# main.net
KiCad netlist of a schematic drawn in Altium Designer
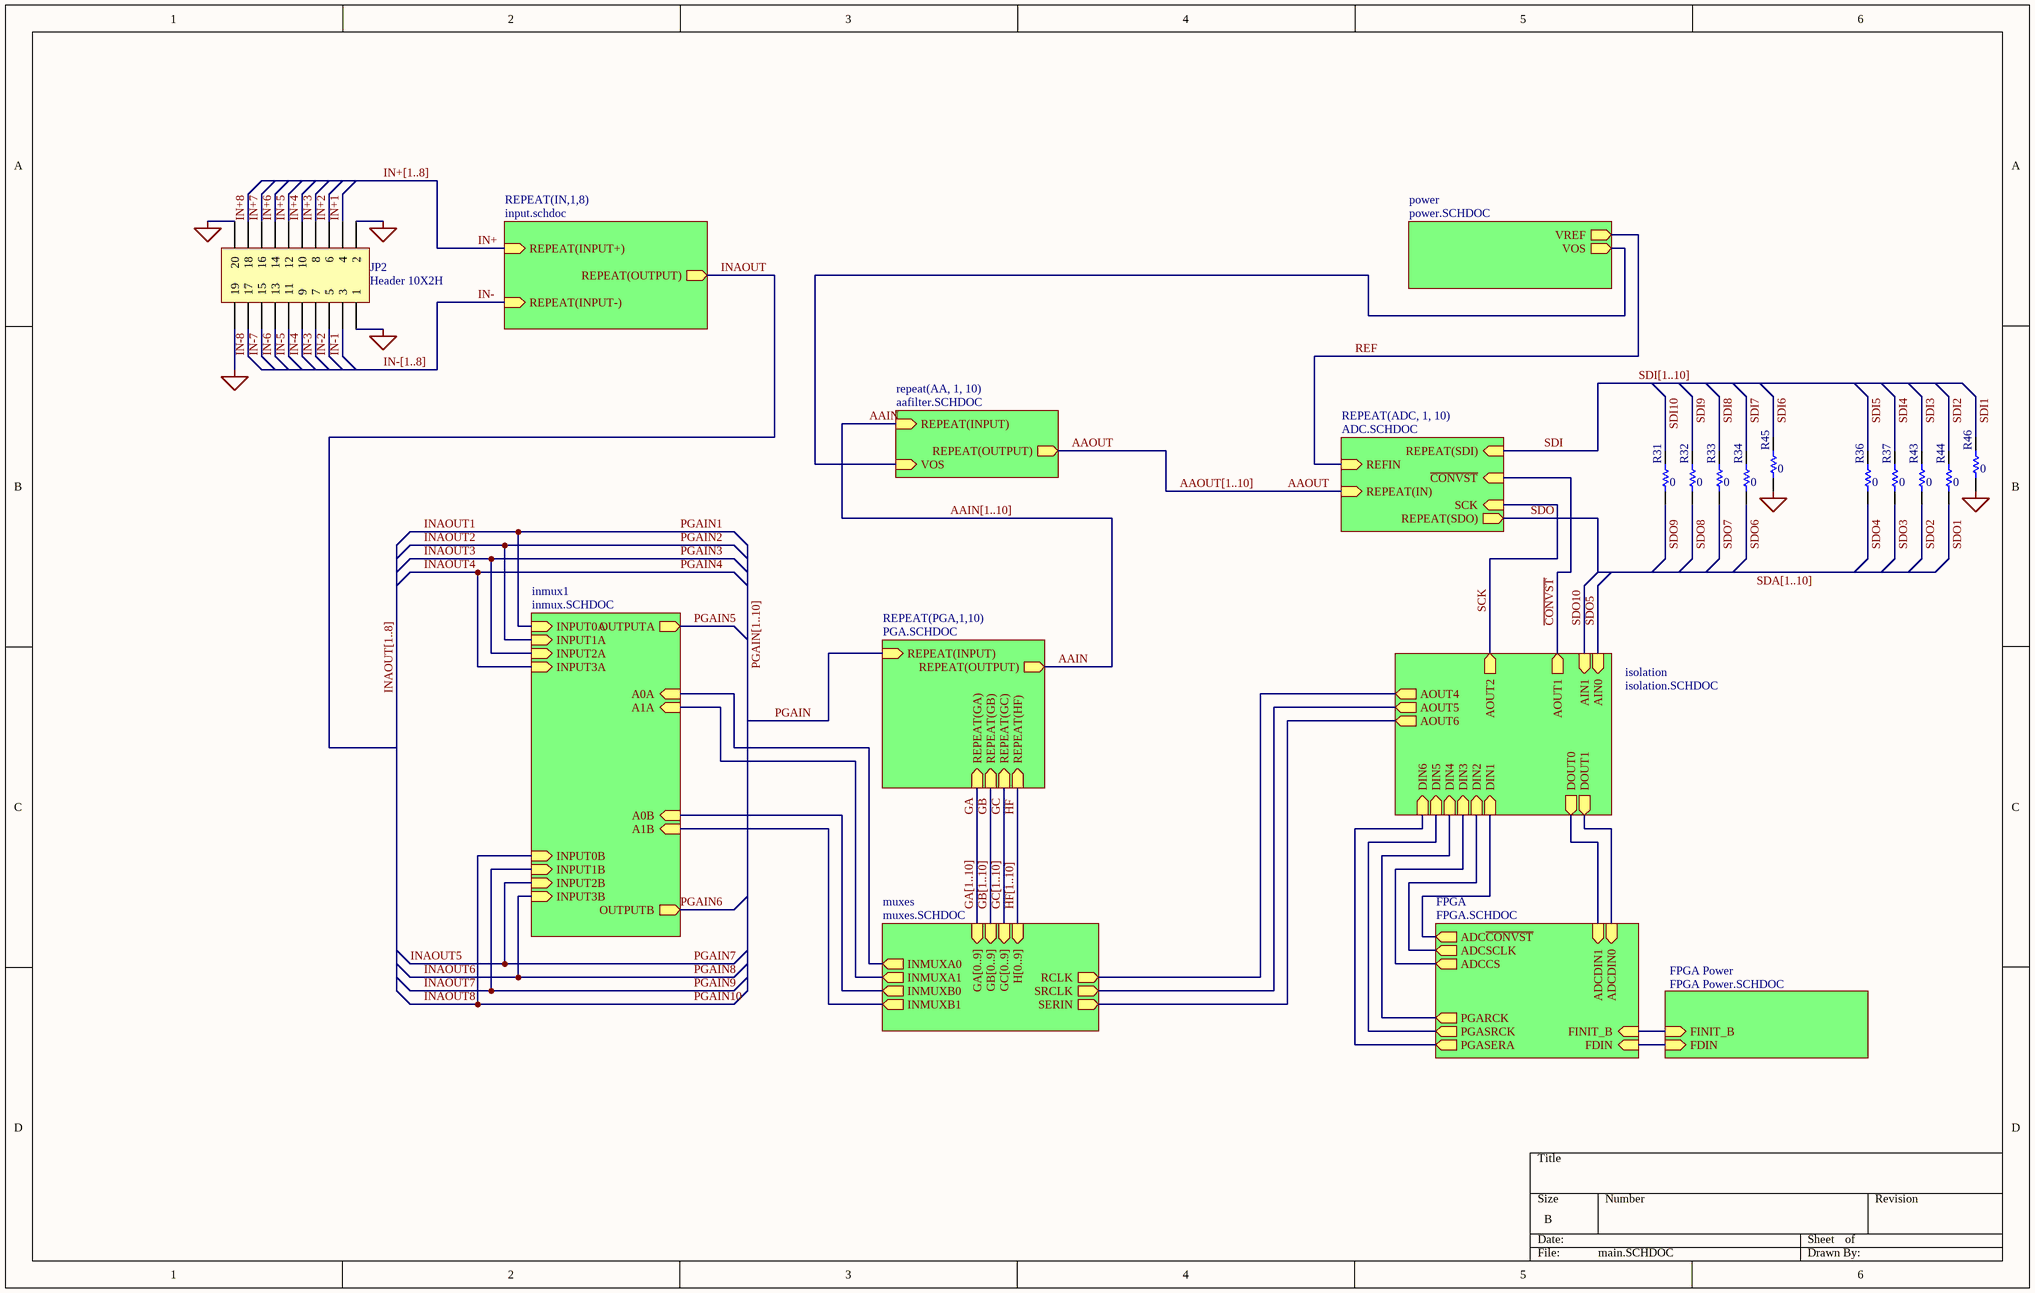
[diagram p0: main.SCHDOC]

(export (version "E")
  (design (tool "Eeschema 10.0.6"))
  (components
    (comp (ref "JP2")
      (value "Header 10X2H")
      (footprint "HDR2X10")
      (description "Header, 10-Pin, Dual row, Right Angle")
      (fields (field (name "MANUFACTURER") "Generic Components") (field (name "PUBLISHER") "Altium Limited"))
      (libsource (lib "Miscellaneous Connectors") (part "Header 10X2H"))
    )
    (comp (ref "R31")
      (value "0")
      (footprint "0603")
      (description "Resistor")
      (fields (field (name "Comment") "Res1") (field (name "PUBLISHER") "Altium Limited"))
      (libsource (lib "Miscellaneous Devices") (part "Res1"))
    )
    (comp (ref "R32")
      (value "0")
      (footprint "0603")
      (description "Resistor")
      (fields (field (name "Comment") "Res1") (field (name "PUBLISHER") "Altium Limited"))
      (libsource (lib "Miscellaneous Devices") (part "Res1"))
    )
    (comp (ref "R33")
      (value "0")
      (footprint "0603")
      (description "Resistor")
      (fields (field (name "Comment") "Res1") (field (name "PUBLISHER") "Altium Limited"))
      (libsource (lib "Miscellaneous Devices") (part "Res1"))
    )
    (comp (ref "R34")
      (value "0")
      (footprint "0603")
      (description "Resistor")
      (fields (field (name "Comment") "Res1") (field (name "PUBLISHER") "Altium Limited"))
      (libsource (lib "Miscellaneous Devices") (part "Res1"))
    )
    (comp (ref "R36")
      (value "0")
      (footprint "0603")
      (description "Resistor")
      (fields (field (name "Comment") "Res1") (field (name "PUBLISHER") "Altium Limited"))
      (libsource (lib "Miscellaneous Devices") (part "Res1"))
    )
    (comp (ref "R37")
      (value "0")
      (footprint "0603")
      (description "Resistor")
      (fields (field (name "Comment") "Res1") (field (name "PUBLISHER") "Altium Limited"))
      (libsource (lib "Miscellaneous Devices") (part "Res1"))
    )
    (comp (ref "R43")
      (value "0")
      (footprint "0603")
      (description "Resistor")
      (fields (field (name "Comment") "Res1") (field (name "PUBLISHER") "Altium Limited"))
      (libsource (lib "Miscellaneous Devices") (part "Res1"))
    )
    (comp (ref "R44")
      (value "0")
      (footprint "0603")
      (description "Resistor")
      (fields (field (name "Comment") "Res1") (field (name "PUBLISHER") "Altium Limited"))
      (libsource (lib "Miscellaneous Devices") (part "Res1"))
    )
    (comp (ref "R45")
      (value "0")
      (footprint "0603")
      (description "Resistor")
      (fields (field (name "Comment") "Res1") (field (name "PUBLISHER") "Altium Limited"))
      (libsource (lib "Miscellaneous Devices") (part "Res1"))
    )
    (comp (ref "R46")
      (value "0")
      (footprint "0603")
      (description "Resistor")
      (fields (field (name "Comment") "Res1") (field (name "PUBLISHER") "Altium Limited"))
      (libsource (lib "Miscellaneous Devices") (part "Res1"))
    )
  )
  (nets
    (net (code "93") (name "/IN+1") (class "Default")
      (node (ref "JP2") (pin "4") (pinfunction "4_4") (pintype "passive"))
    )
    (net (code "94") (name "/IN+2") (class "Default")
      (node (ref "JP2") (pin "6") (pinfunction "6_6") (pintype "passive"))
    )
    (net (code "95") (name "/IN+3") (class "Default")
      (node (ref "JP2") (pin "8") (pinfunction "8_8") (pintype "passive"))
    )
    (net (code "96") (name "/IN+4") (class "Default")
      (node (ref "JP2") (pin "10") (pinfunction "10_10") (pintype "passive"))
    )
    (net (code "97") (name "/IN+5") (class "Default")
      (node (ref "JP2") (pin "12") (pinfunction "12_12") (pintype "passive"))
    )
    (net (code "98") (name "/IN+6") (class "Default")
      (node (ref "JP2") (pin "14") (pinfunction "14_14") (pintype "passive"))
    )
    (net (code "99") (name "/IN+7") (class "Default")
      (node (ref "JP2") (pin "16") (pinfunction "16_16") (pintype "passive"))
    )
    (net (code "100") (name "/IN+8") (class "Default")
      (node (ref "JP2") (pin "18") (pinfunction "18_18") (pintype "passive"))
    )
    (net (code "103") (name "/IN-1") (class "Default")
      (node (ref "JP2") (pin "3") (pinfunction "3_3") (pintype "passive"))
    )
    (net (code "104") (name "/IN-2") (class "Default")
      (node (ref "JP2") (pin "5") (pinfunction "5_5") (pintype "passive"))
    )
    (net (code "105") (name "/IN-3") (class "Default")
      (node (ref "JP2") (pin "7") (pinfunction "7_7") (pintype "passive"))
    )
    (net (code "106") (name "/IN-4") (class "Default")
      (node (ref "JP2") (pin "9") (pinfunction "9_9") (pintype "passive"))
    )
    (net (code "107") (name "/IN-5") (class "Default")
      (node (ref "JP2") (pin "11") (pinfunction "11_11") (pintype "passive"))
    )
    (net (code "108") (name "/IN-6") (class "Default")
      (node (ref "JP2") (pin "13") (pinfunction "13_13") (pintype "passive"))
    )
    (net (code "109") (name "/IN-7") (class "Default")
      (node (ref "JP2") (pin "15") (pinfunction "15_15") (pintype "passive"))
    )
    (net (code "110") (name "/IN-8") (class "Default")
      (node (ref "JP2") (pin "17") (pinfunction "17_17") (pintype "passive"))
    )
    (net (code "138") (name "/SDI1") (class "Default")
      (node (ref "R46") (pin "2") (pinfunction "2_2") (pintype "passive"))
    )
    (net (code "139") (name "/SDI2") (class "Default")
      (node (ref "R44") (pin "2") (pinfunction "2_2") (pintype "passive"))
    )
    (net (code "140") (name "/SDI3") (class "Default")
      (node (ref "R43") (pin "2") (pinfunction "2_2") (pintype "passive"))
    )
    (net (code "141") (name "/SDI4") (class "Default")
      (node (ref "R37") (pin "2") (pinfunction "2_2") (pintype "passive"))
    )
    (net (code "142") (name "/SDI5") (class "Default")
      (node (ref "R36") (pin "2") (pinfunction "2_2") (pintype "passive"))
    )
    (net (code "143") (name "/SDI6") (class "Default")
      (node (ref "R45") (pin "2") (pinfunction "2_2") (pintype "passive"))
    )
    (net (code "144") (name "/SDI7") (class "Default")
      (node (ref "R34") (pin "2") (pinfunction "2_2") (pintype "passive"))
    )
    (net (code "145") (name "/SDI8") (class "Default")
      (node (ref "R33") (pin "2") (pinfunction "2_2") (pintype "passive"))
    )
    (net (code "146") (name "/SDI9") (class "Default")
      (node (ref "R32") (pin "2") (pinfunction "2_2") (pintype "passive"))
    )
    (net (code "147") (name "/SDI10") (class "Default")
      (node (ref "R31") (pin "2") (pinfunction "2_2") (pintype "passive"))
    )
    (net (code "150") (name "/SDO1") (class "Default")
      (node (ref "R44") (pin "1") (pinfunction "1_1") (pintype "passive"))
    )
    (net (code "151") (name "/SDO2") (class "Default")
      (node (ref "R43") (pin "1") (pinfunction "1_1") (pintype "passive"))
    )
    (net (code "152") (name "/SDO3") (class "Default")
      (node (ref "R37") (pin "1") (pinfunction "1_1") (pintype "passive"))
    )
    (net (code "153") (name "/SDO4") (class "Default")
      (node (ref "R36") (pin "1") (pinfunction "1_1") (pintype "passive"))
    )
    (net (code "155") (name "/SDO6") (class "Default")
      (node (ref "R34") (pin "1") (pinfunction "1_1") (pintype "passive"))
    )
    (net (code "156") (name "/SDO7") (class "Default")
      (node (ref "R33") (pin "1") (pinfunction "1_1") (pintype "passive"))
    )
    (net (code "157") (name "/SDO8") (class "Default")
      (node (ref "R32") (pin "1") (pinfunction "1_1") (pintype "passive"))
    )
    (net (code "158") (name "/SDO9") (class "Default")
      (node (ref "R31") (pin "1") (pinfunction "1_1") (pintype "passive"))
    )
    (net (code "162") (name "AGND") (class "Default")
      (node (ref "JP2") (pin "1") (pinfunction "1_1") (pintype "passive"))
      (node (ref "JP2") (pin "19") (pinfunction "19_19") (pintype "passive"))
      (node (ref "JP2") (pin "2") (pinfunction "2_2") (pintype "passive"))
      (node (ref "JP2") (pin "20") (pinfunction "20_20") (pintype "passive"))
      (node (ref "R45") (pin "1") (pinfunction "1_1") (pintype "passive"))
      (node (ref "R46") (pin "1") (pinfunction "1_1") (pintype "passive"))
    )
  )
)
